# BoardB-FPGA3.net
KiCad netlist of a schematic drawn in Altium Designer
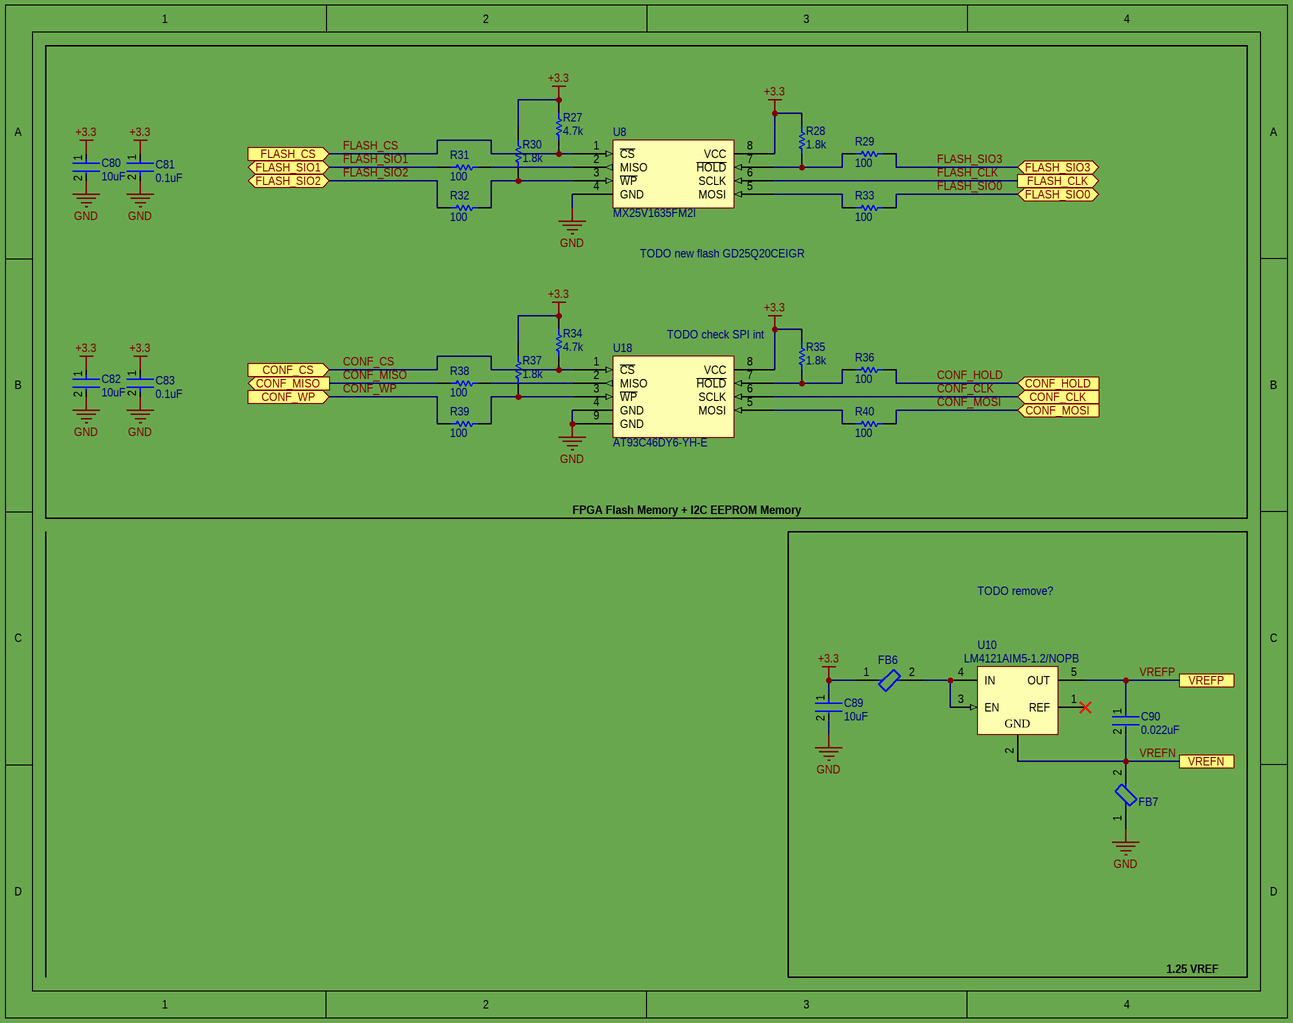
[diagram p0: BoardB-FPGA3.SchDoc]

(export (version "E")
  (design (tool "Eeschema 10.0.6"))
  (components
    (comp (ref "C80")
      (value "10uF")
      (footprint "FP-CL05A106MP5NUNC-MFG")
      (description "CAP CER 10UF 10V X5R 0402")
      (fields
        (field (name "OCTOPART") "https://octopart.com/cl05a106mp5nunc-samsung-22457395")
        (field (name "TOLERANCE") "20%")
      )
      (libsource (lib "Altium Content Vault") (part "b4654b650e69147ec39a6b967a45e02"))
    )
    (comp (ref "C81")
      (value "0.1uF")
      (footprint "FP-GRM15-MFG")
      (description "CAP CER 0.1UF 16V X7R 0402")
      (fields (field (name "MANUFACTURER PART NUMBER") "GRM155R71C104KA88D") (field (name "TOLERANCE") "10%"))
      (libsource (lib "Altium Content Vault") (part "236180d848d6139a670b325ea6854c9"))
    )
    (comp (ref "C82")
      (value "10uF")
      (footprint "FP-CL05A106MP5NUNC-MFG")
      (description "CAP CER 10UF 10V X5R 0402")
      (fields
        (field (name "OCTOPART") "https://octopart.com/cl05a106mp5nunc-samsung-22457395")
        (field (name "TOLERANCE") "20%")
      )
      (libsource (lib "Altium Content Vault") (part "b4654b650e69147ec39a6b967a45e02"))
    )
    (comp (ref "C83")
      (value "0.1uF")
      (footprint "FP-GRM15-MFG")
      (description "CAP CER 0.1UF 16V X7R 0402")
      (fields (field (name "MANUFACTURER PART NUMBER") "GRM155R71C104KA88D") (field (name "TOLERANCE") "10%"))
      (libsource (lib "Altium Content Vault") (part "236180d848d6139a670b325ea6854c9"))
    )
    (comp (ref "C89")
      (value "10uF")
      (footprint "FP-GRM188-0_1-e0_2_0_55-IPC_C")
      (description "Chip Multilayer Ceramic Capacitors for General Purpose, 0603, 10uF, X5R, 15%, 20%, 6.3V")
      (fields (field (name "VOLTAGE") "6.3V") (field (name "TOLERANCE") "20%"))
      (libsource (lib "Altium Content Vault") (part "02cd4be3c70576c341d710602a673aa"))
    )
    (comp (ref "C90")
      (value "0.022uF")
      (footprint "FP-CC0402-MFG")
      (description "CAP CER 0.022UF 16V X7R 0402")
      (fields
        (field (name "OCTOPART") "https://octopart.com/cc0402krx7r7bb223-yageo-42244626")
        (field (name "MANUFACTURER PART NUMBER") "CC0402KRX7R7BB223")
      )
      (libsource (lib "Altium Content Vault") (part "11868f565c42a9108669ba33697ecf6"))
    )
    (comp (ref "FB6")
      (value "BLM18AG601SN1D")
      (footprint "FP-BLM18-0_15-t0_8-MFG")
      (description "Chip Ferrite Bead, 0603, 600Ω @ 100MHz, 0.38Ω, 25%, 500mA")
      (fields (field (name "TOLERANCE") "25%"))
      (libsource (lib "Altium Content Vault") (part "5f30dd21d616792df468990f7003faa"))
    )
    (comp (ref "FB7")
      (value "BLM18AG601SN1D")
      (footprint "FP-BLM18-0_15-t0_8-MFG")
      (description "Chip Ferrite Bead, 0603, 600Ω @ 100MHz, 0.38Ω, 25%, 500mA")
      (fields (field (name "TOLERANCE") "25%"))
      (libsource (lib "Altium Content Vault") (part "5f30dd21d616792df468990f7003faa"))
    )
    (comp (ref "R27")
      (value "4.7k")
      (footprint "RESC1005X40X25NL05T05")
      (description "Chip Resistor, 4.7 KOhm, +/- 1%, 0.1 W, -55 to 155 degC, 0402 (1005 Metric), RoHS, Tape and Reel")
      (fields (field (name "TOLERANCE") "1%") (field (name "PARTNUMBER") "ERJ-2RKF4701X"))
      (libsource (lib "Altium Content Vault") (part "RES-2"))
    )
    (comp (ref "R28")
      (value "1.8k")
      (footprint "RESC1005X40X25LL05T05")
      (fields (field (name "MANUFACTURER") "Panasonic") (field (name "PART NUMBER") "ERJ2RKF1801X"))
      (libsource (lib "Altium Content Vault") (part "RES"))
    )
    (comp (ref "R29")
      (value "100")
      (footprint "RESC1005X40X25LL05T05")
      (description "Chip Resistor, 100 Ohm, +/- 1%, 100 mW, -55 to 155 degC, 0402 (1005 Metric), RoHS, Tape and Reel")
      (fields (field (name "MANUFACTURER") "Basic Passives") (field (name "TOLERANCE") "1%"))
      (libsource (lib "Altium Content Vault") (part "RES-2"))
    )
    (comp (ref "R30")
      (value "1.8k")
      (footprint "RESC1005X40X25LL05T05")
      (fields (field (name "MANUFACTURER") "Panasonic") (field (name "PART NUMBER") "ERJ2RKF1801X"))
      (libsource (lib "Altium Content Vault") (part "RES"))
    )
    (comp (ref "R31")
      (value "100")
      (footprint "RESC1005X40X25LL05T05")
      (description "Chip Resistor, 100 Ohm, +/- 1%, 100 mW, -55 to 155 degC, 0402 (1005 Metric), RoHS, Tape and Reel")
      (fields (field (name "MANUFACTURER") "Basic Passives") (field (name "TOLERANCE") "1%"))
      (libsource (lib "Altium Content Vault") (part "RES-2"))
    )
    (comp (ref "R32")
      (value "100")
      (footprint "RESC1005X40X25LL05T05")
      (description "Chip Resistor, 100 Ohm, +/- 1%, 100 mW, -55 to 155 degC, 0402 (1005 Metric), RoHS, Tape and Reel")
      (fields (field (name "MANUFACTURER") "Basic Passives") (field (name "TOLERANCE") "1%"))
      (libsource (lib "Altium Content Vault") (part "RES-2"))
    )
    (comp (ref "R33")
      (value "100")
      (footprint "RESC1005X40X25LL05T05")
      (description "Chip Resistor, 100 Ohm, +/- 1%, 100 mW, -55 to 155 degC, 0402 (1005 Metric), RoHS, Tape and Reel")
      (fields (field (name "MANUFACTURER") "Basic Passives") (field (name "TOLERANCE") "1%"))
      (libsource (lib "Altium Content Vault") (part "RES-2"))
    )
    (comp (ref "R34")
      (value "4.7k")
      (footprint "RESC1005X40X25NL05T05")
      (description "Chip Resistor, 4.7 KOhm, +/- 1%, 0.1 W, -55 to 155 degC, 0402 (1005 Metric), RoHS, Tape and Reel")
      (fields (field (name "TOLERANCE") "1%") (field (name "PARTNUMBER") "ERJ-2RKF4701X"))
      (libsource (lib "Altium Content Vault") (part "RES-2"))
    )
    (comp (ref "R35")
      (value "1.8k")
      (footprint "RESC1005X40X25LL05T05")
      (fields (field (name "MANUFACTURER") "Panasonic") (field (name "PART NUMBER") "ERJ2RKF1801X"))
      (libsource (lib "Altium Content Vault") (part "RES"))
    )
    (comp (ref "R36")
      (value "100")
      (footprint "RESC1005X40X25LL05T05")
      (description "Chip Resistor, 100 Ohm, +/- 1%, 100 mW, -55 to 155 degC, 0402 (1005 Metric), RoHS, Tape and Reel")
      (fields (field (name "MANUFACTURER") "Basic Passives") (field (name "TOLERANCE") "1%"))
      (libsource (lib "Altium Content Vault") (part "RES-2"))
    )
    (comp (ref "R37")
      (value "1.8k")
      (footprint "RESC1005X40X25LL05T05")
      (fields (field (name "MANUFACTURER") "Panasonic") (field (name "PART NUMBER") "ERJ2RKF1801X"))
      (libsource (lib "Altium Content Vault") (part "RES"))
    )
    (comp (ref "R38")
      (value "100")
      (footprint "RESC1005X40X25LL05T05")
      (description "Chip Resistor, 100 Ohm, +/- 1%, 100 mW, -55 to 155 degC, 0402 (1005 Metric), RoHS, Tape and Reel")
      (fields (field (name "MANUFACTURER") "Basic Passives") (field (name "TOLERANCE") "1%"))
      (libsource (lib "Altium Content Vault") (part "RES-2"))
    )
    (comp (ref "R39")
      (value "100")
      (footprint "RESC1005X40X25LL05T05")
      (description "Chip Resistor, 100 Ohm, +/- 1%, 100 mW, -55 to 155 degC, 0402 (1005 Metric), RoHS, Tape and Reel")
      (fields (field (name "MANUFACTURER") "Basic Passives") (field (name "TOLERANCE") "1%"))
      (libsource (lib "Altium Content Vault") (part "RES-2"))
    )
    (comp (ref "R40")
      (value "100")
      (footprint "RESC1005X40X25LL05T05")
      (description "Chip Resistor, 100 Ohm, +/- 1%, 100 mW, -55 to 155 degC, 0402 (1005 Metric), RoHS, Tape and Reel")
      (fields (field (name "MANUFACTURER") "Basic Passives") (field (name "TOLERANCE") "1%"))
      (libsource (lib "Altium Content Vault") (part "RES-2"))
    )
    (comp (ref "U8")
      (value "MX25V1635FM2I")
      (footprint "MX25V1635FM2I")
      (description "IC FLASH 16M SPI 80MHZ 8SOP")
      (fields (field (name "MANUFACTURER") "Macronix"))
      (libsource (lib "Virtex") (part "MX25V1635FM2I"))
    )
    (comp (ref "U10")
      (value "LM4121AIM5-1.2/NOPB")
      (footprint "MF05A_M")
      (description "Precision Micropower Low Dropout Voltage Reference, 5-pin SOT-23, Pb-Free")
      (fields (field (name "MANUFACTURER") "National Semiconductor"))
      (libsource (lib "Altium Content Vault") (part "PM-REF-LM4120-SOT5"))
    )
    (comp (ref "U18")
      (value "AT93C46DY6-YH-E")
      (footprint "AT93C46DY6-YH-E")
      (description "EEPROM Memory IC 1Kb (128 x 8, 64 x 16) SPI 8-UDFN (2x3)")
      (fields
        (field (name "MANUFACTURER") "Microchip")
        (field (name "MANUFACTURER PART NUMBER") "AT25040B-MAHL-E")
      )
      (libsource (lib "Virtex") (part "AT93C46DY6-YH-E"))
    )
  )
  (nets
    (net (code "1") (name "+3.3") (class "Default")
      (node (ref "C80") (pin "1") (pinfunction "1_1") (pintype "passive"))
      (node (ref "C81") (pin "1") (pinfunction "1_1") (pintype "passive"))
      (node (ref "C82") (pin "1") (pinfunction "1_1") (pintype "passive"))
      (node (ref "C83") (pin "1") (pinfunction "1_1") (pintype "passive"))
      (node (ref "C89") (pin "1") (pinfunction "1_1") (pintype "passive"))
      (node (ref "FB6") (pin "1") (pinfunction "1_1") (pintype "passive"))
      (node (ref "R27") (pin "2") (pinfunction "2_2") (pintype "passive"))
      (node (ref "R28") (pin "2") (pinfunction "2_2") (pintype "passive"))
      (node (ref "R30") (pin "2") (pinfunction "2_2") (pintype "passive"))
      (node (ref "R34") (pin "2") (pinfunction "2_2") (pintype "passive"))
      (node (ref "R35") (pin "2") (pinfunction "2_2") (pintype "passive"))
      (node (ref "R37") (pin "2") (pinfunction "2_2") (pintype "passive"))
      (node (ref "U18") (pin "8") (pinfunction "VCC_8") (pintype "power_in"))
      (node (ref "U8") (pin "8") (pinfunction "VCC_8") (pintype "power_in"))
    )
    (net (code "2") (name "/CONF_CLK") (class "Default")
      (node (ref "U18") (pin "6") (pinfunction "SCLK_6") (pintype "input"))
    )
    (net (code "3") (name "/CONF_CS") (class "Default")
      (node (ref "R34") (pin "1") (pinfunction "1_1") (pintype "passive"))
      (node (ref "U18") (pin "1") (pinfunction "~{CS}_1") (pintype "input"))
    )
    (net (code "4") (name "/CONF_HOLD") (class "Default")
      (node (ref "R36") (pin "2") (pinfunction "2_2") (pintype "passive"))
    )
    (net (code "5") (name "/CONF_MISO") (class "Default")
      (node (ref "R38") (pin "1") (pinfunction "1_1") (pintype "passive"))
    )
    (net (code "6") (name "/CONF_MOSI") (class "Default")
      (node (ref "R40") (pin "2") (pinfunction "2_2") (pintype "passive"))
    )
    (net (code "7") (name "/CONF_WP") (class "Default")
      (node (ref "R39") (pin "1") (pinfunction "1_1") (pintype "passive"))
    )
    (net (code "8") (name "/FLASH_CLK") (class "Default")
      (node (ref "U8") (pin "6") (pinfunction "SCLK_6") (pintype "input"))
    )
    (net (code "9") (name "/FLASH_CS") (class "Default")
      (node (ref "R27") (pin "1") (pinfunction "1_1") (pintype "passive"))
      (node (ref "U8") (pin "1") (pinfunction "~{CS}_1") (pintype "input"))
    )
    (net (code "10") (name "/FLASH_SIO0") (class "Default")
      (node (ref "R33") (pin "2") (pinfunction "2_2") (pintype "passive"))
    )
    (net (code "11") (name "/FLASH_SIO1") (class "Default")
      (node (ref "R31") (pin "1") (pinfunction "1_1") (pintype "passive"))
    )
    (net (code "12") (name "/FLASH_SIO2") (class "Default")
      (node (ref "R32") (pin "1") (pinfunction "1_1") (pintype "passive"))
    )
    (net (code "13") (name "/FLASH_SIO3") (class "Default")
      (node (ref "R29") (pin "2") (pinfunction "2_2") (pintype "passive"))
    )
    (net (code "14") (name "/VREFN") (class "Default")
      (node (ref "C90") (pin "2") (pinfunction "2_2") (pintype "passive"))
      (node (ref "FB7") (pin "2") (pinfunction "2_2") (pintype "passive"))
      (node (ref "U10") (pin "2") (pinfunction "GND_2") (pintype "power_in"))
    )
    (net (code "15") (name "/VREFP") (class "Default")
      (node (ref "C90") (pin "1") (pinfunction "1_1") (pintype "passive"))
      (node (ref "U10") (pin "5") (pinfunction "OUT_5") (pintype "power_in"))
    )
    (net (code "16") (name "GND") (class "Default")
      (node (ref "C80") (pin "2") (pinfunction "2_2") (pintype "passive"))
      (node (ref "C81") (pin "2") (pinfunction "2_2") (pintype "passive"))
      (node (ref "C82") (pin "2") (pinfunction "2_2") (pintype "passive"))
      (node (ref "C83") (pin "2") (pinfunction "2_2") (pintype "passive"))
      (node (ref "C89") (pin "2") (pinfunction "2_2") (pintype "passive"))
      (node (ref "FB7") (pin "1") (pinfunction "1_1") (pintype "passive"))
      (node (ref "U18") (pin "4") (pinfunction "GND_4") (pintype "power_in"))
      (node (ref "U18") (pin "9") (pinfunction "GND_9") (pintype "power_in"))
      (node (ref "U8") (pin "4") (pinfunction "GND_4") (pintype "power_in"))
    )
    (net (code "17") (name "Net-(U8-MISO)") (class "Default")
      (node (ref "R31") (pin "2") (pinfunction "2_2") (pintype "passive"))
      (node (ref "U8") (pin "2") (pinfunction "MISO_2") (pintype "output"))
    )
    (net (code "18") (name "Net-(U8-MOSI)") (class "Default")
      (node (ref "R33") (pin "1") (pinfunction "1_1") (pintype "passive"))
      (node (ref "U8") (pin "5") (pinfunction "MOSI_5") (pintype "input"))
    )
    (net (code "19") (name "Net-(U8-~{HOLD})") (class "Default")
      (node (ref "R28") (pin "1") (pinfunction "1_1") (pintype "passive"))
      (node (ref "R29") (pin "1") (pinfunction "1_1") (pintype "passive"))
      (node (ref "U8") (pin "7") (pinfunction "~{HOLD}_7") (pintype "input"))
    )
    (net (code "20") (name "Net-(U8-~{WP})") (class "Default")
      (node (ref "R30") (pin "1") (pinfunction "1_1") (pintype "passive"))
      (node (ref "R32") (pin "2") (pinfunction "2_2") (pintype "passive"))
      (node (ref "U8") (pin "3") (pinfunction "~{WP}_3") (pintype "input"))
    )
    (net (code "21") (name "Net-(U10-EN)") (class "Default")
      (node (ref "FB6") (pin "2") (pinfunction "2_2") (pintype "passive"))
      (node (ref "U10") (pin "3") (pinfunction "EN_3") (pintype "input"))
      (node (ref "U10") (pin "4") (pinfunction "IN_4") (pintype "power_in"))
    )
    (net (code "22") (name "Net-(U18-MISO)") (class "Default")
      (node (ref "R38") (pin "2") (pinfunction "2_2") (pintype "passive"))
      (node (ref "U18") (pin "2") (pinfunction "MISO_2") (pintype "output"))
    )
    (net (code "23") (name "Net-(U18-MOSI)") (class "Default")
      (node (ref "R40") (pin "1") (pinfunction "1_1") (pintype "passive"))
      (node (ref "U18") (pin "5") (pinfunction "MOSI_5") (pintype "input"))
    )
    (net (code "24") (name "Net-(U18-~{HOLD})") (class "Default")
      (node (ref "R35") (pin "1") (pinfunction "1_1") (pintype "passive"))
      (node (ref "R36") (pin "1") (pinfunction "1_1") (pintype "passive"))
      (node (ref "U18") (pin "7") (pinfunction "~{HOLD}_7") (pintype "input"))
    )
    (net (code "25") (name "Net-(U18-~{WP})") (class "Default")
      (node (ref "R37") (pin "1") (pinfunction "1_1") (pintype "passive"))
      (node (ref "R39") (pin "2") (pinfunction "2_2") (pintype "passive"))
      (node (ref "U18") (pin "3") (pinfunction "~{WP}_3") (pintype "input"))
    )
    (net (code "26") (name "unconnected-(U10-REF-Pad1)") (class "Default")
      (node (ref "U10") (pin "1") (pinfunction "REF_1") (pintype "passive+no_connect"))
    )
  )
)
